# pneumatic_horse.net
KiCad netlist of a schematic drawn in EAGLE
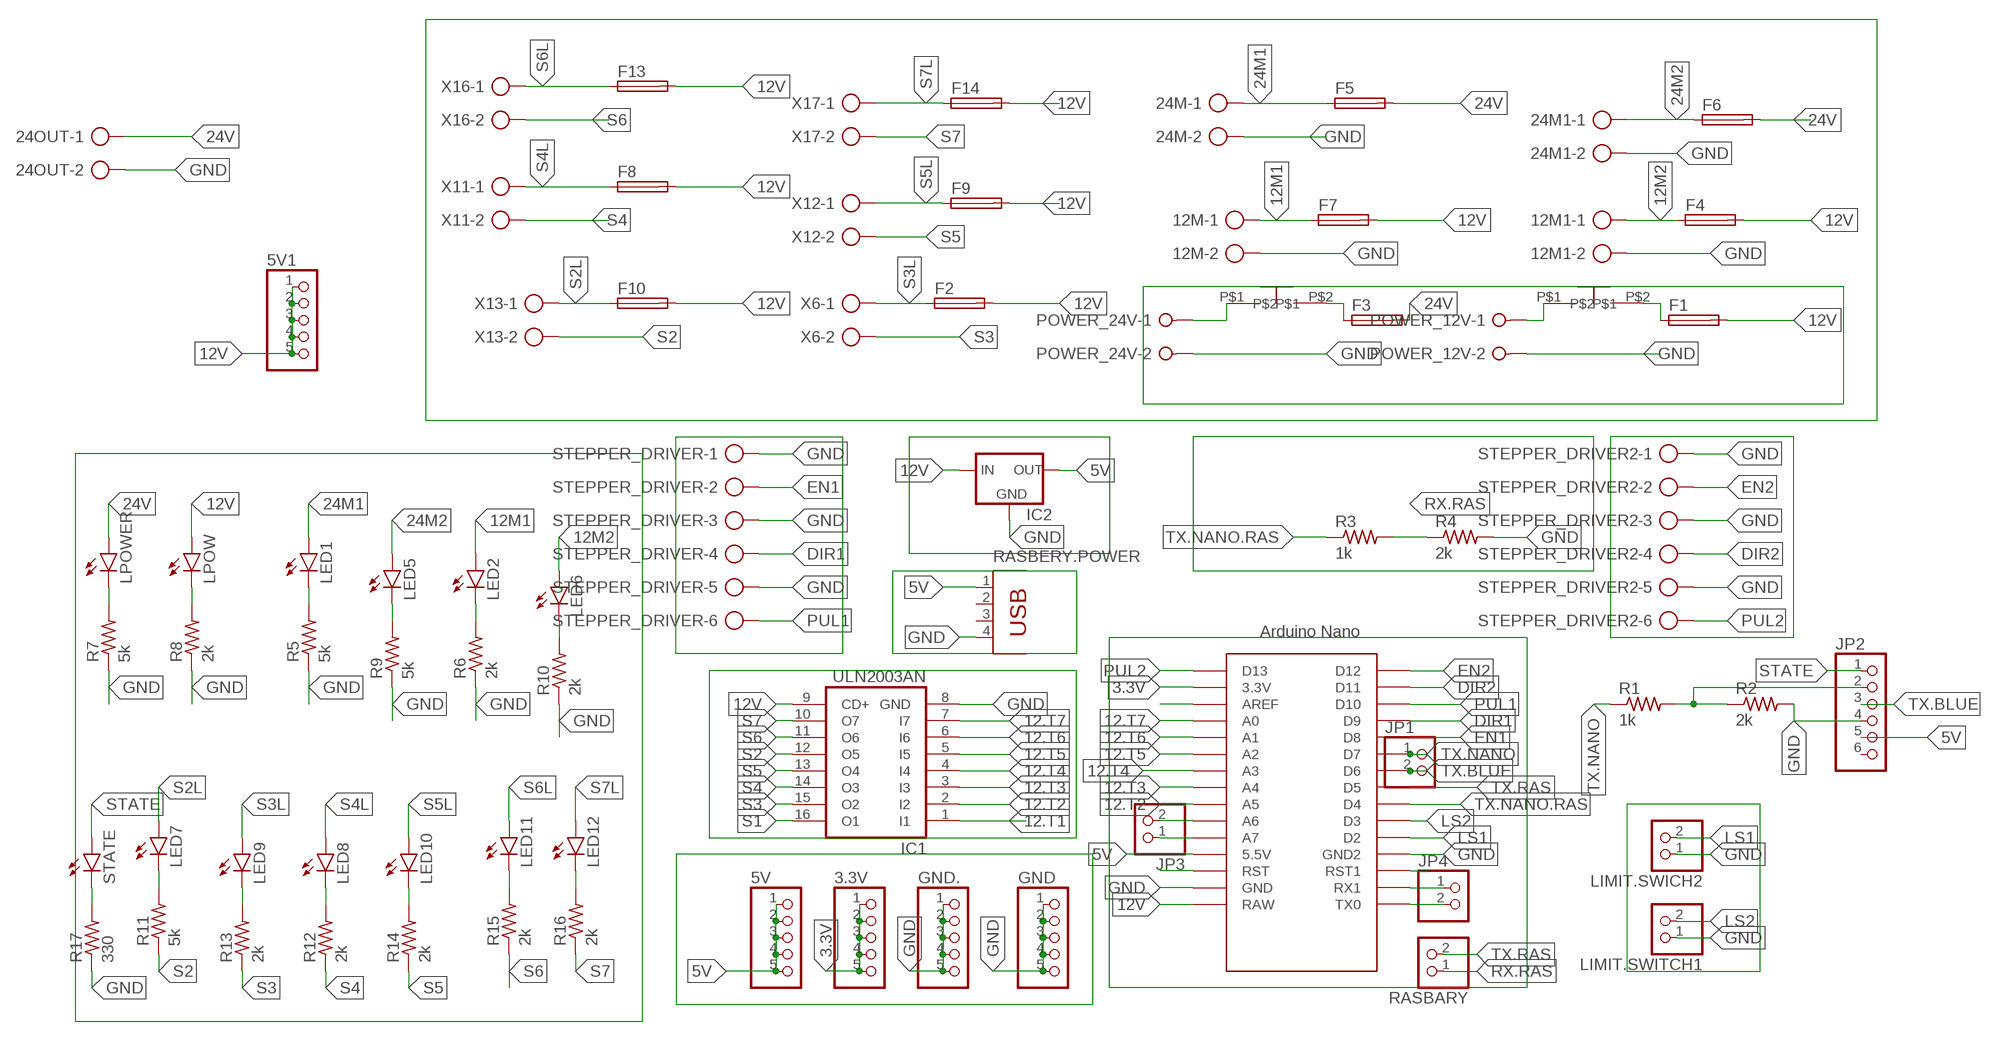
[diagram p0: schematic, sheet 1]

(export (version "E")
  (design (tool "Eeschema 10.0.6"))
  (components
    (comp (ref "3.3V")
      (value "PINHD-1X5")
      (footprint "eagle-import:1X05")
      (libsource (lib "eagle-import") (part "PINHD-1X5"))
    )
    (comp (ref "5V")
      (value "PINHD-1X5")
      (footprint "eagle-import:1X05")
      (libsource (lib "eagle-import") (part "PINHD-1X5"))
    )
    (comp (ref "5V1")
      (value "PINHD-1X5")
      (footprint "eagle-import:1X05")
      (libsource (lib "eagle-import") (part "PINHD-1X5"))
    )
    (comp (ref "12M")
      (value "AK300/2")
      (footprint "eagle-import:AK300_2")
      (libsource (lib "eagle-import") (part "AK300/2"))
    )
    (comp (ref "12M1")
      (value "AK300/2")
      (footprint "eagle-import:AK300_2")
      (libsource (lib "eagle-import") (part "AK300/2"))
    )
    (comp (ref "24M")
      (value "AK300/2")
      (footprint "eagle-import:AK300_2")
      (libsource (lib "eagle-import") (part "AK300/2"))
    )
    (comp (ref "24M1")
      (value "AK300/2")
      (footprint "eagle-import:AK300_2")
      (libsource (lib "eagle-import") (part "AK300/2"))
    )
    (comp (ref "24OUT")
      (value "AK300/2")
      (footprint "eagle-import:AK300_2")
      (libsource (lib "eagle-import") (part "AK300/2"))
    )
    (comp (ref "F1")
      (value "SH22,5A")
      (footprint "eagle-import:SH22,5A")
      (fields (field (name "MPN") "0031.7701.11"))
      (libsource (lib "eagle-import") (part "SH22,5A"))
    )
    (comp (ref "F2")
      (value "SH22,5A")
      (footprint "eagle-import:SH22,5A")
      (fields (field (name "MPN") "0031.7701.11"))
      (libsource (lib "eagle-import") (part "SH22,5A"))
    )
    (comp (ref "F3")
      (value "SH22,5A")
      (footprint "eagle-import:SH22,5A")
      (fields (field (name "MPN") "0031.7701.11"))
      (libsource (lib "eagle-import") (part "SH22,5A"))
    )
    (comp (ref "F4")
      (value "SH22,5A")
      (footprint "eagle-import:SH22,5A")
      (fields (field (name "MPN") "0031.7701.11"))
      (libsource (lib "eagle-import") (part "SH22,5A"))
    )
    (comp (ref "F5")
      (value "SH22,5A")
      (footprint "eagle-import:SH22,5A")
      (fields (field (name "MPN") "0031.7701.11"))
      (libsource (lib "eagle-import") (part "SH22,5A"))
    )
    (comp (ref "F6")
      (value "SH22,5A")
      (footprint "eagle-import:SH22,5A")
      (fields (field (name "MPN") "0031.7701.11"))
      (libsource (lib "eagle-import") (part "SH22,5A"))
    )
    (comp (ref "F7")
      (value "SH22,5A")
      (footprint "eagle-import:SH22,5A")
      (fields (field (name "MPN") "0031.7701.11"))
      (libsource (lib "eagle-import") (part "SH22,5A"))
    )
    (comp (ref "F8")
      (value "SH22,5A")
      (footprint "eagle-import:SH22,5A")
      (fields (field (name "MPN") "0031.7701.11"))
      (libsource (lib "eagle-import") (part "SH22,5A"))
    )
    (comp (ref "F9")
      (value "SH22,5A")
      (footprint "eagle-import:SH22,5A")
      (fields (field (name "MPN") "0031.7701.11"))
      (libsource (lib "eagle-import") (part "SH22,5A"))
    )
    (comp (ref "F10")
      (value "SH22,5A")
      (footprint "eagle-import:SH22,5A")
      (fields (field (name "MPN") "0031.7701.11"))
      (libsource (lib "eagle-import") (part "SH22,5A"))
    )
    (comp (ref "F13")
      (value "SH22,5A")
      (footprint "eagle-import:SH22,5A")
      (fields (field (name "MPN") "0031.7701.11"))
      (libsource (lib "eagle-import") (part "SH22,5A"))
    )
    (comp (ref "F14")
      (value "SH22,5A")
      (footprint "eagle-import:SH22,5A")
      (fields (field (name "MPN") "0031.7701.11"))
      (libsource (lib "eagle-import") (part "SH22,5A"))
    )
    (comp (ref "GND")
      (value "PINHD-1X5")
      (footprint "eagle-import:1X05")
      (libsource (lib "eagle-import") (part "PINHD-1X5"))
    )
    (comp (ref "GND.")
      (value "PINHD-1X5")
      (footprint "eagle-import:1X05")
      (libsource (lib "eagle-import") (part "PINHD-1X5"))
    )
    (comp (ref "IC1")
      (value "ULN2003AN")
      (footprint "eagle-import:DIL16")
      (libsource (lib "eagle-import") (part "ULN2003AN"))
    )
    (comp (ref "IC2")
      (value "78XXS")
      (footprint "eagle-import:78XXS")
      (libsource (lib "eagle-import") (part "78XXS"))
    )
    (comp (ref "JP1")
      (value "PINHD-1X2")
      (footprint "eagle-import:1X02")
      (libsource (lib "eagle-import") (part "PINHD-1X2"))
    )
    (comp (ref "JP2")
      (value "PINHD-1X6")
      (footprint "eagle-import:1X06")
      (libsource (lib "eagle-import") (part "PINHD-1X6"))
    )
    (comp (ref "JP3")
      (value "PINHD-1X2")
      (footprint "eagle-import:1X02")
      (libsource (lib "eagle-import") (part "PINHD-1X2"))
    )
    (comp (ref "JP4")
      (value "PINHD-1X2")
      (footprint "eagle-import:1X02")
      (libsource (lib "eagle-import") (part "PINHD-1X2"))
    )
    (comp (ref "LED1")
      (value "LED3MM")
      (footprint "eagle-import:LED3MM")
      (libsource (lib "eagle-import") (part "LED3MM"))
    )
    (comp (ref "LED2")
      (value "LED3MM")
      (footprint "eagle-import:LED3MM")
      (libsource (lib "eagle-import") (part "LED3MM"))
    )
    (comp (ref "LED5")
      (value "LED3MM")
      (footprint "eagle-import:LED3MM")
      (libsource (lib "eagle-import") (part "LED3MM"))
    )
    (comp (ref "LED6")
      (value "LED3MM")
      (footprint "eagle-import:LED3MM")
      (libsource (lib "eagle-import") (part "LED3MM"))
    )
    (comp (ref "LED7")
      (value "LED3MM")
      (footprint "eagle-import:LED3MM")
      (libsource (lib "eagle-import") (part "LED3MM"))
    )
    (comp (ref "LED8")
      (value "LED3MM")
      (footprint "eagle-import:LED3MM")
      (libsource (lib "eagle-import") (part "LED3MM"))
    )
    (comp (ref "LED9")
      (value "LED3MM")
      (footprint "eagle-import:LED3MM")
      (libsource (lib "eagle-import") (part "LED3MM"))
    )
    (comp (ref "LED10")
      (value "LED3MM")
      (footprint "eagle-import:LED3MM")
      (libsource (lib "eagle-import") (part "LED3MM"))
    )
    (comp (ref "LED11")
      (value "LED3MM")
      (footprint "eagle-import:LED3MM")
      (libsource (lib "eagle-import") (part "LED3MM"))
    )
    (comp (ref "LED12")
      (value "LED3MM")
      (footprint "eagle-import:LED3MM")
      (libsource (lib "eagle-import") (part "LED3MM"))
    )
    (comp (ref "LIMIT.SWICH2")
      (value "PINHD-1X2")
      (footprint "eagle-import:1X02")
      (libsource (lib "eagle-import") (part "PINHD-1X2"))
    )
    (comp (ref "LIMIT.SWITCH1")
      (value "PINHD-1X2")
      (footprint "eagle-import:1X02")
      (libsource (lib "eagle-import") (part "PINHD-1X2"))
    )
    (comp (ref "LPOW")
      (value "LED5MM")
      (footprint "eagle-import:LED5MM")
      (libsource (lib "eagle-import") (part "LED5MM"))
    )
    (comp (ref "LPOWER")
      (value "LED3MM")
      (footprint "eagle-import:LED3MM")
      (libsource (lib "eagle-import") (part "LED3MM"))
    )
    (comp (ref "POWER_12V")
      (value "W237-2N")
      (footprint "eagle-import:W237-2N")
      (libsource (lib "eagle-import") (part "W237-2N"))
    )
    (comp (ref "POWER_24V")
      (value "W237-2N")
      (footprint "eagle-import:W237-2N")
      (libsource (lib "eagle-import") (part "W237-2N"))
    )
    (comp (ref "R1")
      (value "1k")
      (footprint "eagle-import:0204_7")
      (libsource (lib "eagle-import") (part "R-US_0204/7"))
    )
    (comp (ref "R2")
      (value "2k")
      (footprint "eagle-import:0204_7")
      (libsource (lib "eagle-import") (part "R-US_0204/7"))
    )
    (comp (ref "R3")
      (value "1k")
      (footprint "eagle-import:0204_7")
      (libsource (lib "eagle-import") (part "R-US_0204/7"))
    )
    (comp (ref "R4")
      (value "2k")
      (footprint "eagle-import:0204_7")
      (libsource (lib "eagle-import") (part "R-US_0204/7"))
    )
    (comp (ref "R5")
      (value "5k")
      (footprint "eagle-import:0204_7")
      (libsource (lib "eagle-import") (part "R-US_0204/7"))
    )
    (comp (ref "R6")
      (value "2k")
      (footprint "eagle-import:0204_7")
      (libsource (lib "eagle-import") (part "R-US_0204/7"))
    )
    (comp (ref "R7")
      (value "5k")
      (footprint "eagle-import:0204_7")
      (libsource (lib "eagle-import") (part "R-US_0204/7"))
    )
    (comp (ref "R8")
      (value "2k")
      (footprint "eagle-import:0204_7")
      (libsource (lib "eagle-import") (part "R-US_0204/7"))
    )
    (comp (ref "R9")
      (value "5k")
      (footprint "eagle-import:0204_7")
      (libsource (lib "eagle-import") (part "R-US_0204/7"))
    )
    (comp (ref "R10")
      (value "2k")
      (footprint "eagle-import:0204_7")
      (libsource (lib "eagle-import") (part "R-US_0204/7"))
    )
    (comp (ref "R11")
      (value "5k")
      (footprint "eagle-import:0204_5")
      (libsource (lib "eagle-import") (part "R-US_0204/5"))
    )
    (comp (ref "R12")
      (value "2k")
      (footprint "eagle-import:0204_5")
      (libsource (lib "eagle-import") (part "R-US_0204/5"))
    )
    (comp (ref "R13")
      (value "2k")
      (footprint "eagle-import:0204_5")
      (libsource (lib "eagle-import") (part "R-US_0204/5"))
    )
    (comp (ref "R14")
      (value "2k")
      (footprint "eagle-import:0204_5")
      (libsource (lib "eagle-import") (part "R-US_0204/5"))
    )
    (comp (ref "R15")
      (value "2k")
      (footprint "eagle-import:0204_5")
      (libsource (lib "eagle-import") (part "R-US_0204/5"))
    )
    (comp (ref "R16")
      (value "2k")
      (footprint "eagle-import:0204_5")
      (libsource (lib "eagle-import") (part "R-US_0204/5"))
    )
    (comp (ref "R17")
      (value "330")
      (footprint "eagle-import:0204_5")
      (libsource (lib "eagle-import") (part "R-US_0204/5"))
    )
    (comp (ref "RASBARY")
      (value "PINHD-1X2")
      (footprint "eagle-import:1X02")
      (libsource (lib "eagle-import") (part "PINHD-1X2"))
    )
    (comp (ref "RASBERY.POWER")
      (value "PN87520")
      (footprint "eagle-import:PN87520")
      (libsource (lib "eagle-import") (part "PN87520"))
    )
    (comp (ref "STATE")
      (value "LED3MM")
      (footprint "eagle-import:LED3MM")
      (libsource (lib "eagle-import") (part "LED3MM"))
    )
    (comp (ref "STEPPER_DRIVER")
      (value "AK300/6")
      (footprint "eagle-import:AK300_6")
      (libsource (lib "eagle-import") (part "AK300/6"))
    )
    (comp (ref "STEPPER_DRIVER2")
      (value "AK300/6")
      (footprint "eagle-import:AK300_6")
      (libsource (lib "eagle-import") (part "AK300/6"))
    )
    (comp (ref "U$1")
      (value "NANO")
      (footprint "eagle-import:NANO")
      (libsource (lib "eagle-import") (part "NANO"))
    )
    (comp (ref "U$2")
      (value "ON_OFF")
      (footprint "eagle-import:ON_OFF")
      (libsource (lib "eagle-import") (part "ON_OFF"))
    )
    (comp (ref "U$3")
      (value "ON_OFF")
      (footprint "eagle-import:ON_OFF")
      (libsource (lib "eagle-import") (part "ON_OFF"))
    )
    (comp (ref "X6")
      (value "AK300/2")
      (footprint "eagle-import:AK300_2")
      (libsource (lib "eagle-import") (part "AK300/2"))
    )
    (comp (ref "X11")
      (value "AK300/2")
      (footprint "eagle-import:AK300_2")
      (libsource (lib "eagle-import") (part "AK300/2"))
    )
    (comp (ref "X12")
      (value "AK300/2")
      (footprint "eagle-import:AK300_2")
      (libsource (lib "eagle-import") (part "AK300/2"))
    )
    (comp (ref "X13")
      (value "AK300/2")
      (footprint "eagle-import:AK300_2")
      (libsource (lib "eagle-import") (part "AK300/2"))
    )
    (comp (ref "X16")
      (value "AK300/2")
      (footprint "eagle-import:AK300_2")
      (libsource (lib "eagle-import") (part "AK300/2"))
    )
    (comp (ref "X17")
      (value "AK300/2")
      (footprint "eagle-import:AK300_2")
      (libsource (lib "eagle-import") (part "AK300/2"))
    )
  )
  (nets
    (net (code "1") (name "3.3V") (class "Default")
      (node (ref "3.3V") (pin "1") (pinfunction "1_1") (pintype "passive"))
      (node (ref "3.3V") (pin "2") (pinfunction "2_2") (pintype "passive"))
      (node (ref "3.3V") (pin "3") (pinfunction "3_3") (pintype "passive"))
      (node (ref "3.3V") (pin "4") (pinfunction "4_4") (pintype "passive"))
      (node (ref "3.3V") (pin "5") (pinfunction "5_5") (pintype "passive"))
      (node (ref "U$1") (pin "3.3V") (pinfunction "3.3V_3.3V") (pintype "bidirectional"))
    )
    (net (code "2") (name "5V") (class "Default")
      (node (ref "5V") (pin "1") (pinfunction "1_1") (pintype "passive"))
      (node (ref "5V") (pin "2") (pinfunction "2_2") (pintype "passive"))
      (node (ref "5V") (pin "3") (pinfunction "3_3") (pintype "passive"))
      (node (ref "5V") (pin "4") (pinfunction "4_4") (pintype "passive"))
      (node (ref "5V") (pin "5") (pinfunction "5_5") (pintype "passive"))
      (node (ref "IC2") (pin "OUT") (pinfunction "OUT_OUT") (pintype "passive"))
      (node (ref "JP2") (pin "5") (pinfunction "5_5") (pintype "passive"))
      (node (ref "RASBERY.POWER") (pin "1") (pinfunction "1_1") (pintype "passive"))
      (node (ref "U$1") (pin "5V") (pinfunction "5.5V_5V") (pintype "bidirectional"))
    )
    (net (code "3") (name "12.T1") (class "Default")
      (node (ref "IC1") (pin "1") (pinfunction "I1_1") (pintype "input"))
    )
    (net (code "4") (name "12.T2") (class "Default")
      (node (ref "IC1") (pin "2") (pinfunction "I2_2") (pintype "input"))
      (node (ref "U$1") (pin "A5") (pinfunction "A5_A5") (pintype "bidirectional"))
    )
    (net (code "5") (name "12.T3") (class "Default")
      (node (ref "IC1") (pin "3") (pinfunction "I3_3") (pintype "input"))
      (node (ref "U$1") (pin "A4") (pinfunction "A4_A4") (pintype "bidirectional"))
    )
    (net (code "6") (name "12.T4") (class "Default")
      (node (ref "IC1") (pin "4") (pinfunction "I4_4") (pintype "input"))
      (node (ref "U$1") (pin "A3") (pinfunction "A3_A3") (pintype "bidirectional"))
    )
    (net (code "7") (name "12.T5") (class "Default")
      (node (ref "IC1") (pin "5") (pinfunction "I5_5") (pintype "input"))
      (node (ref "U$1") (pin "A2") (pinfunction "A2_A2") (pintype "bidirectional"))
    )
    (net (code "8") (name "12.T6") (class "Default")
      (node (ref "IC1") (pin "6") (pinfunction "I6_6") (pintype "input"))
      (node (ref "U$1") (pin "A1") (pinfunction "A1_A1") (pintype "bidirectional"))
    )
    (net (code "9") (name "12.T7") (class "Default")
      (node (ref "IC1") (pin "7") (pinfunction "I7_7") (pintype "input"))
      (node (ref "U$1") (pin "A0") (pinfunction "A0_A0") (pintype "bidirectional"))
    )
    (net (code "10") (name "12M1") (class "Default")
      (node (ref "12M") (pin "1") (pinfunction "KL_1") (pintype "passive"))
      (node (ref "F7") (pin "1") (pinfunction "1_1") (pintype "passive"))
      (node (ref "LED2") (pin "A") (pinfunction "A_A") (pintype "passive"))
    )
    (net (code "11") (name "12M2") (class "Default")
      (node (ref "12M1") (pin "1") (pinfunction "KL_1") (pintype "passive"))
      (node (ref "F4") (pin "1") (pinfunction "1_1") (pintype "passive"))
      (node (ref "LED6") (pin "A") (pinfunction "A_A") (pintype "passive"))
    )
    (net (code "12") (name "12V") (class "Default")
      (node (ref "5V1") (pin "1") (pinfunction "1_1") (pintype "passive"))
      (node (ref "5V1") (pin "2") (pinfunction "2_2") (pintype "passive"))
      (node (ref "5V1") (pin "3") (pinfunction "3_3") (pintype "passive"))
      (node (ref "5V1") (pin "4") (pinfunction "4_4") (pintype "passive"))
      (node (ref "5V1") (pin "5") (pinfunction "5_5") (pintype "passive"))
      (node (ref "F1") (pin "2") (pinfunction "2_2") (pintype "passive"))
      (node (ref "F10") (pin "2") (pinfunction "2_2") (pintype "passive"))
      (node (ref "F13") (pin "2") (pinfunction "2_2") (pintype "passive"))
      (node (ref "F14") (pin "2") (pinfunction "2_2") (pintype "passive"))
      (node (ref "F2") (pin "2") (pinfunction "2_2") (pintype "passive"))
      (node (ref "F4") (pin "2") (pinfunction "2_2") (pintype "passive"))
      (node (ref "F7") (pin "2") (pinfunction "2_2") (pintype "passive"))
      (node (ref "F8") (pin "2") (pinfunction "2_2") (pintype "passive"))
      (node (ref "F9") (pin "2") (pinfunction "2_2") (pintype "passive"))
      (node (ref "IC1") (pin "9") (pinfunction "CD+_9") (pintype "passive"))
      (node (ref "IC2") (pin "IN") (pinfunction "IN_IN") (pintype "input"))
      (node (ref "LPOW") (pin "A") (pinfunction "A_A") (pintype "passive"))
      (node (ref "U$1") (pin "RAW") (pinfunction "RAW_RAW") (pintype "bidirectional"))
    )
    (net (code "13") (name "24M1") (class "Default")
      (node (ref "24M") (pin "1") (pinfunction "KL_1") (pintype "passive"))
      (node (ref "F5") (pin "1") (pinfunction "1_1") (pintype "passive"))
      (node (ref "LED1") (pin "A") (pinfunction "A_A") (pintype "passive"))
    )
    (net (code "14") (name "24M2") (class "Default")
      (node (ref "24M1") (pin "1") (pinfunction "KL_1") (pintype "passive"))
      (node (ref "F6") (pin "1") (pinfunction "1_1") (pintype "passive"))
      (node (ref "LED5") (pin "A") (pinfunction "A_A") (pintype "passive"))
    )
    (net (code "15") (name "24V") (class "Default")
      (node (ref "24OUT") (pin "1") (pinfunction "KL_1") (pintype "passive"))
      (node (ref "F3") (pin "2") (pinfunction "2_2") (pintype "passive"))
      (node (ref "F5") (pin "2") (pinfunction "2_2") (pintype "passive"))
      (node (ref "F6") (pin "2") (pinfunction "2_2") (pintype "passive"))
      (node (ref "LPOWER") (pin "A") (pinfunction "A_A") (pintype "passive"))
    )
    (net (code "16") (name "DIR1") (class "Default")
      (node (ref "STEPPER_DRIVER") (pin "4") (pinfunction "KL_4") (pintype "passive"))
      (node (ref "U$1") (pin "D9") (pinfunction "D9_D9") (pintype "bidirectional"))
    )
    (net (code "17") (name "DIR2") (class "Default")
      (node (ref "STEPPER_DRIVER2") (pin "4") (pinfunction "KL_4") (pintype "passive"))
      (node (ref "U$1") (pin "D11") (pinfunction "D11_D11") (pintype "bidirectional"))
    )
    (net (code "18") (name "EN1") (class "Default")
      (node (ref "STEPPER_DRIVER") (pin "2") (pinfunction "KL_2") (pintype "passive"))
      (node (ref "U$1") (pin "D8") (pinfunction "D8_D8") (pintype "bidirectional"))
    )
    (net (code "19") (name "EN2") (class "Default")
      (node (ref "STEPPER_DRIVER2") (pin "2") (pinfunction "KL_2") (pintype "passive"))
      (node (ref "U$1") (pin "D12") (pinfunction "D12_D12") (pintype "bidirectional"))
    )
    (net (code "20") (name "GND") (class "Default")
      (node (ref "12M") (pin "2") (pinfunction "KL_2") (pintype "passive"))
      (node (ref "12M1") (pin "2") (pinfunction "KL_2") (pintype "passive"))
      (node (ref "24M") (pin "2") (pinfunction "KL_2") (pintype "passive"))
      (node (ref "24M1") (pin "2") (pinfunction "KL_2") (pintype "passive"))
      (node (ref "24OUT") (pin "2") (pinfunction "KL_2") (pintype "passive"))
      (node (ref "GND") (pin "1") (pinfunction "1_1") (pintype "passive"))
      (node (ref "GND") (pin "2") (pinfunction "2_2") (pintype "passive"))
      (node (ref "GND") (pin "3") (pinfunction "3_3") (pintype "passive"))
      (node (ref "GND") (pin "4") (pinfunction "4_4") (pintype "passive"))
      (node (ref "GND") (pin "5") (pinfunction "5_5") (pintype "passive"))
      (node (ref "GND.") (pin "1") (pinfunction "1_1") (pintype "passive"))
      (node (ref "GND.") (pin "2") (pinfunction "2_2") (pintype "passive"))
      (node (ref "GND.") (pin "3") (pinfunction "3_3") (pintype "passive"))
      (node (ref "GND.") (pin "4") (pinfunction "4_4") (pintype "passive"))
      (node (ref "GND.") (pin "5") (pinfunction "5_5") (pintype "passive"))
      (node (ref "IC1") (pin "8") (pinfunction "GND_8") (pintype "power_in"))
      (node (ref "IC2") (pin "GND") (pinfunction "GND_GND") (pintype "input"))
      (node (ref "JP2") (pin "4") (pinfunction "4_4") (pintype "passive"))
      (node (ref "LIMIT.SWICH2") (pin "1") (pinfunction "1_1") (pintype "passive"))
      (node (ref "LIMIT.SWITCH1") (pin "1") (pinfunction "1_1") (pintype "passive"))
      (node (ref "POWER_12V") (pin "2") (pinfunction "KL_2") (pintype "passive"))
      (node (ref "POWER_24V") (pin "2") (pinfunction "KL_2") (pintype "passive"))
      (node (ref "R10") (pin "1") (pinfunction "1_1") (pintype "passive"))
      (node (ref "R17") (pin "1") (pinfunction "1_1") (pintype "passive"))
      (node (ref "R2") (pin "2") (pinfunction "2_2") (pintype "passive"))
      (node (ref "R4") (pin "2") (pinfunction "2_2") (pintype "passive"))
      (node (ref "R5") (pin "1") (pinfunction "1_1") (pintype "passive"))
      (node (ref "R6") (pin "1") (pinfunction "1_1") (pintype "passive"))
      (node (ref "R7") (pin "1") (pinfunction "1_1") (pintype "passive"))
      (node (ref "R8") (pin "1") (pinfunction "1_1") (pintype "passive"))
      (node (ref "R9") (pin "1") (pinfunction "1_1") (pintype "passive"))
      (node (ref "RASBERY.POWER") (pin "4") (pinfunction "4_4") (pintype "passive"))
      (node (ref "STEPPER_DRIVER") (pin "1") (pinfunction "KL_1") (pintype "passive"))
      (node (ref "STEPPER_DRIVER") (pin "3") (pinfunction "KL_3") (pintype "passive"))
      (node (ref "STEPPER_DRIVER") (pin "5") (pinfunction "KL_5") (pintype "passive"))
      (node (ref "STEPPER_DRIVER2") (pin "1") (pinfunction "KL_1") (pintype "passive"))
      (node (ref "STEPPER_DRIVER2") (pin "3") (pinfunction "KL_3") (pintype "passive"))
      (node (ref "STEPPER_DRIVER2") (pin "5") (pinfunction "KL_5") (pintype "passive"))
      (node (ref "U$1") (pin "GND") (pinfunction "GND_GND") (pintype "bidirectional"))
      (node (ref "U$1") (pin "GND1") (pinfunction "GND2_GND1") (pintype "bidirectional"))
    )
    (net (code "21") (name "LS1") (class "Default")
      (node (ref "LIMIT.SWICH2") (pin "2") (pinfunction "2_2") (pintype "passive"))
      (node (ref "U$1") (pin "D2") (pinfunction "D2_D2") (pintype "bidirectional"))
    )
    (net (code "22") (name "LS2") (class "Default")
      (node (ref "LIMIT.SWITCH1") (pin "2") (pinfunction "2_2") (pintype "passive"))
      (node (ref "U$1") (pin "D3") (pinfunction "D3_D3") (pintype "bidirectional"))
    )
    (net (code "23") (name "Net-(F1-Pad1)") (class "Default")
      (node (ref "F1") (pin "1") (pinfunction "1_1") (pintype "passive"))
      (node (ref "U$3") (pin "P$2") (pinfunction "P$2_P$2") (pintype "bidirectional"))
    )
    (net (code "24") (name "Net-(F3-Pad1)") (class "Default")
      (node (ref "F3") (pin "1") (pinfunction "1_1") (pintype "passive"))
      (node (ref "U$2") (pin "P$2") (pinfunction "P$2_P$2") (pintype "bidirectional"))
    )
    (net (code "25") (name "Net-(JP2-Pad2)") (class "Default")
      (node (ref "JP2") (pin "2") (pinfunction "2_2") (pintype "passive"))
      (node (ref "R1") (pin "2") (pinfunction "2_2") (pintype "passive"))
      (node (ref "R2") (pin "1") (pinfunction "1_1") (pintype "passive"))
    )
    (net (code "26") (name "Net-(JP3-Pad1)") (class "Default")
      (node (ref "JP3") (pin "1") (pinfunction "1_1") (pintype "passive"))
      (node (ref "U$1") (pin "A7") (pinfunction "A7_A7") (pintype "bidirectional"))
    )
    (net (code "27") (name "Net-(JP3-Pad2)") (class "Default")
      (node (ref "JP3") (pin "2") (pinfunction "2_2") (pintype "passive"))
      (node (ref "U$1") (pin "A6") (pinfunction "A6_A6") (pintype "bidirectional"))
    )
    (net (code "28") (name "Net-(JP4-Pad1)") (class "Default")
      (node (ref "JP4") (pin "1") (pinfunction "1_1") (pintype "passive"))
      (node (ref "U$1") (pin "RX1") (pinfunction "RX1_RX1") (pintype "bidirectional"))
    )
    (net (code "29") (name "Net-(JP4-Pad2)") (class "Default")
      (node (ref "JP4") (pin "2") (pinfunction "2_2") (pintype "passive"))
      (node (ref "U$1") (pin "TX0") (pinfunction "TX0_TX0") (pintype "bidirectional"))
    )
    (net (code "30") (name "Net-(LED1-C)") (class "Default")
      (node (ref "LED1") (pin "K") (pinfunction "C_K") (pintype "passive"))
      (node (ref "R5") (pin "2") (pinfunction "2_2") (pintype "passive"))
    )
    (net (code "31") (name "Net-(LED2-C)") (class "Default")
      (node (ref "LED2") (pin "K") (pinfunction "C_K") (pintype "passive"))
      (node (ref "R6") (pin "2") (pinfunction "2_2") (pintype "passive"))
    )
    (net (code "32") (name "Net-(LED5-C)") (class "Default")
      (node (ref "LED5") (pin "K") (pinfunction "C_K") (pintype "passive"))
      (node (ref "R9") (pin "2") (pinfunction "2_2") (pintype "passive"))
    )
    (net (code "33") (name "Net-(LED6-C)") (class "Default")
      (node (ref "LED6") (pin "K") (pinfunction "C_K") (pintype "passive"))
      (node (ref "R10") (pin "2") (pinfunction "2_2") (pintype "passive"))
    )
    (net (code "34") (name "Net-(LED7-C)") (class "Default")
      (node (ref "LED7") (pin "K") (pinfunction "C_K") (pintype "passive"))
      (node (ref "R11") (pin "2") (pinfunction "2_2") (pintype "passive"))
    )
    (net (code "35") (name "Net-(LED8-C)") (class "Default")
      (node (ref "LED8") (pin "K") (pinfunction "C_K") (pintype "passive"))
      (node (ref "R12") (pin "2") (pinfunction "2_2") (pintype "passive"))
    )
    (net (code "36") (name "Net-(LED9-C)") (class "Default")
      (node (ref "LED9") (pin "K") (pinfunction "C_K") (pintype "passive"))
      (node (ref "R13") (pin "2") (pinfunction "2_2") (pintype "passive"))
    )
    (net (code "37") (name "Net-(LED10-C)") (class "Default")
      (node (ref "LED10") (pin "K") (pinfunction "C_K") (pintype "passive"))
      (node (ref "R14") (pin "2") (pinfunction "2_2") (pintype "passive"))
    )
    (net (code "38") (name "Net-(LED11-C)") (class "Default")
      (node (ref "LED11") (pin "K") (pinfunction "C_K") (pintype "passive"))
      (node (ref "R15") (pin "2") (pinfunction "2_2") (pintype "passive"))
    )
    (net (code "39") (name "Net-(LED12-C)") (class "Default")
      (node (ref "LED12") (pin "K") (pinfunction "C_K") (pintype "passive"))
      (node (ref "R16") (pin "2") (pinfunction "2_2") (pintype "passive"))
    )
    (net (code "40") (name "Net-(LPOW-C)") (class "Default")
      (node (ref "LPOW") (pin "K") (pinfunction "C_K") (pintype "passive"))
      (node (ref "R8") (pin "2") (pinfunction "2_2") (pintype "passive"))
    )
    (net (code "41") (name "Net-(LPOWER-C)") (class "Default")
      (node (ref "LPOWER") (pin "K") (pinfunction "C_K") (pintype "passive"))
      (node (ref "R7") (pin "2") (pinfunction "2_2") (pintype "passive"))
    )
    (net (code "42") (name "Net-(POWER_12VA-KL)") (class "Default")
      (node (ref "POWER_12V") (pin "1") (pinfunction "KL_1") (pintype "passive"))
      (node (ref "U$3") (pin "P$1") (pinfunction "P$1_P$1") (pintype "bidirectional"))
    )
    (net (code "43") (name "Net-(POWER_24VA-KL)") (class "Default")
      (node (ref "POWER_24V") (pin "1") (pinfunction "KL_1") (pintype "passive"))
      (node (ref "U$2") (pin "P$1") (pinfunction "P$1_P$1") (pintype "bidirectional"))
    )
    (net (code "44") (name "Net-(STATE-C)") (class "Default")
      (node (ref "R17") (pin "2") (pinfunction "2_2") (pintype "passive"))
      (node (ref "STATE") (pin "K") (pinfunction "C_K") (pintype "passive"))
    )
    (net (code "45") (name "PUL1") (class "Default")
      (node (ref "STEPPER_DRIVER") (pin "6") (pinfunction "KL_6") (pintype "passive"))
      (node (ref "U$1") (pin "D10") (pinfunction "D10_D10") (pintype "bidirectional"))
    )
    (net (code "46") (name "PUL2") (class "Default")
      (node (ref "STEPPER_DRIVER2") (pin "6") (pinfunction "KL_6") (pintype "passive"))
      (node (ref "U$1") (pin "D13") (pinfunction "D13_D13") (pintype "bidirectional"))
    )
    (net (code "47") (name "RX.RAS") (class "Default")
      (node (ref "R3") (pin "2") (pinfunction "2_2") (pintype "passive"))
      (node (ref "R4") (pin "1") (pinfunction "1_1") (pintype "passive"))
      (node (ref "RASBARY") (pin "1") (pinfunction "1_1") (pintype "passive"))
    )
    (net (code "48") (name "S1") (class "Default")
      (node (ref "IC1") (pin "16") (pinfunction "O1_16") (pintype "open_collector"))
    )
    (net (code "49") (name "S2") (class "Default")
      (node (ref "IC1") (pin "12") (pinfunction "O5_12") (pintype "open_collector"))
      (node (ref "R11") (pin "1") (pinfunction "1_1") (pintype "passive"))
      (node (ref "X13") (pin "2") (pinfunction "KL_2") (pintype "passive"))
    )
    (net (code "50") (name "S2L") (class "Default")
      (node (ref "F10") (pin "1") (pinfunction "1_1") (pintype "passive"))
      (node (ref "LED7") (pin "A") (pinfunction "A_A") (pintype "passive"))
      (node (ref "X13") (pin "1") (pinfunction "KL_1") (pintype "passive"))
    )
    (net (code "51") (name "S3") (class "Default")
      (node (ref "IC1") (pin "15") (pinfunction "O2_15") (pintype "open_collector"))
      (node (ref "R13") (pin "1") (pinfunction "1_1") (pintype "passive"))
      (node (ref "X6") (pin "2") (pinfunction "KL_2") (pintype "passive"))
    )
    (net (code "52") (name "S3L") (class "Default")
      (node (ref "F2") (pin "1") (pinfunction "1_1") (pintype "passive"))
      (node (ref "LED9") (pin "A") (pinfunction "A_A") (pintype "passive"))
      (node (ref "X6") (pin "1") (pinfunction "KL_1") (pintype "passive"))
    )
    (net (code "53") (name "S4") (class "Default")
      (node (ref "IC1") (pin "14") (pinfunction "O3_14") (pintype "open_collector"))
      (node (ref "R12") (pin "1") (pinfunction "1_1") (pintype "passive"))
      (node (ref "X11") (pin "2") (pinfunction "KL_2") (pintype "passive"))
    )
    (net (code "54") (name "S4L") (class "Default")
      (node (ref "F8") (pin "1") (pinfunction "1_1") (pintype "passive"))
      (node (ref "LED8") (pin "A") (pinfunction "A_A") (pintype "passive"))
      (node (ref "X11") (pin "1") (pinfunction "KL_1") (pintype "passive"))
    )
    (net (code "55") (name "S5") (class "Default")
      (node (ref "IC1") (pin "13") (pinfunction "O4_13") (pintype "open_collector"))
      (node (ref "R14") (pin "1") (pinfunction "1_1") (pintype "passive"))
      (node (ref "X12") (pin "2") (pinfunction "KL_2") (pintype "passive"))
    )
    (net (code "56") (name "S5L") (class "Default")
      (node (ref "F9") (pin "1") (pinfunction "1_1") (pintype "passive"))
      (node (ref "LED10") (pin "A") (pinfunction "A_A") (pintype "passive"))
      (node (ref "X12") (pin "1") (pinfunction "KL_1") (pintype "passive"))
    )
    (net (code "57") (name "S6") (class "Default")
      (node (ref "IC1") (pin "11") (pinfunction "O6_11") (pintype "open_collector"))
      (node (ref "R15") (pin "1") (pinfunction "1_1") (pintype "passive"))
      (node (ref "X16") (pin "2") (pinfunction "KL_2") (pintype "passive"))
    )
    (net (code "58") (name "S6L") (class "Default")
      (node (ref "F13") (pin "1") (pinfunction "1_1") (pintype "passive"))
      (node (ref "LED11") (pin "A") (pinfunction "A_A") (pintype "passive"))
      (node (ref "X16") (pin "1") (pinfunction "KL_1") (pintype "passive"))
    )
    (net (code "59") (name "S7") (class "Default")
      (node (ref "IC1") (pin "10") (pinfunction "O7_10") (pintype "open_collector"))
      (node (ref "R16") (pin "1") (pinfunction "1_1") (pintype "passive"))
      (node (ref "X17") (pin "2") (pinfunction "KL_2") (pintype "passive"))
    )
    (net (code "60") (name "S7L") (class "Default")
      (node (ref "F14") (pin "1") (pinfunction "1_1") (pintype "passive"))
      (node (ref "LED12") (pin "A") (pinfunction "A_A") (pintype "passive"))
      (node (ref "X17") (pin "1") (pinfunction "KL_1") (pintype "passive"))
    )
    (net (code "61") (name "STATE") (class "Default")
      (node (ref "JP2") (pin "1") (pinfunction "1_1") (pintype "passive"))
      (node (ref "STATE") (pin "A") (pinfunction "A_A") (pintype "passive"))
    )
    (net (code "62") (name "TX.BLUE") (class "Default")
      (node (ref "JP1") (pin "2") (pinfunction "2_2") (pintype "passive"))
      (node (ref "JP2") (pin "3") (pinfunction "3_3") (pintype "passive"))
      (node (ref "U$1") (pin "D6") (pinfunction "D6_D6") (pintype "bidirectional"))
    )
    (net (code "63") (name "TX.NANO") (class "Default")
      (node (ref "JP1") (pin "1") (pinfunction "1_1") (pintype "passive"))
      (node (ref "R1") (pin "1") (pinfunction "1_1") (pintype "passive"))
      (node (ref "U$1") (pin "D7") (pinfunction "D7_D7") (pintype "bidirectional"))
    )
    (net (code "64") (name "TX.NANO.RAS") (class "Default")
      (node (ref "R3") (pin "1") (pinfunction "1_1") (pintype "passive"))
      (node (ref "U$1") (pin "D4") (pinfunction "D4_D4") (pintype "bidirectional"))
    )
    (net (code "65") (name "TX.RAS") (class "Default")
      (node (ref "RASBARY") (pin "2") (pinfunction "2_2") (pintype "passive"))
      (node (ref "U$1") (pin "D5") (pinfunction "D5_D5") (pintype "bidirectional"))
    )
    (net (code "66") (name "unconnected-(JP2-Pad6)") (class "Default")
      (node (ref "JP2") (pin "6") (pinfunction "6_6") (pintype "passive"))
    )
    (net (code "67") (name "unconnected-(RASBERY.POWER-Pad2)") (class "Default")
      (node (ref "RASBERY.POWER") (pin "2") (pinfunction "2_2") (pintype "passive"))
    )
    (net (code "68") (name "unconnected-(RASBERY.POWER-Pad3)") (class "Default")
      (node (ref "RASBERY.POWER") (pin "3") (pinfunction "3_3") (pintype "passive"))
    )
    (net (code "69") (name "unconnected-(U$1-PadAREF)") (class "Default")
      (node (ref "U$1") (pin "AREF") (pinfunction "AREF_AREF") (pintype "bidirectional"))
    )
    (net (code "70") (name "unconnected-(U$1-PadRST)") (class "Default")
      (node (ref "U$1") (pin "RST") (pinfunction "RST_RST") (pintype "bidirectional"))
    )
    (net (code "71") (name "unconnected-(U$1-PadRST1)") (class "Default")
      (node (ref "U$1") (pin "RST1") (pinfunction "RST1_RST1") (pintype "bidirectional"))
    )
  )
)
